# DCMotor1CTRL.net
KiCad netlist of a schematic drawn in Altium Designer
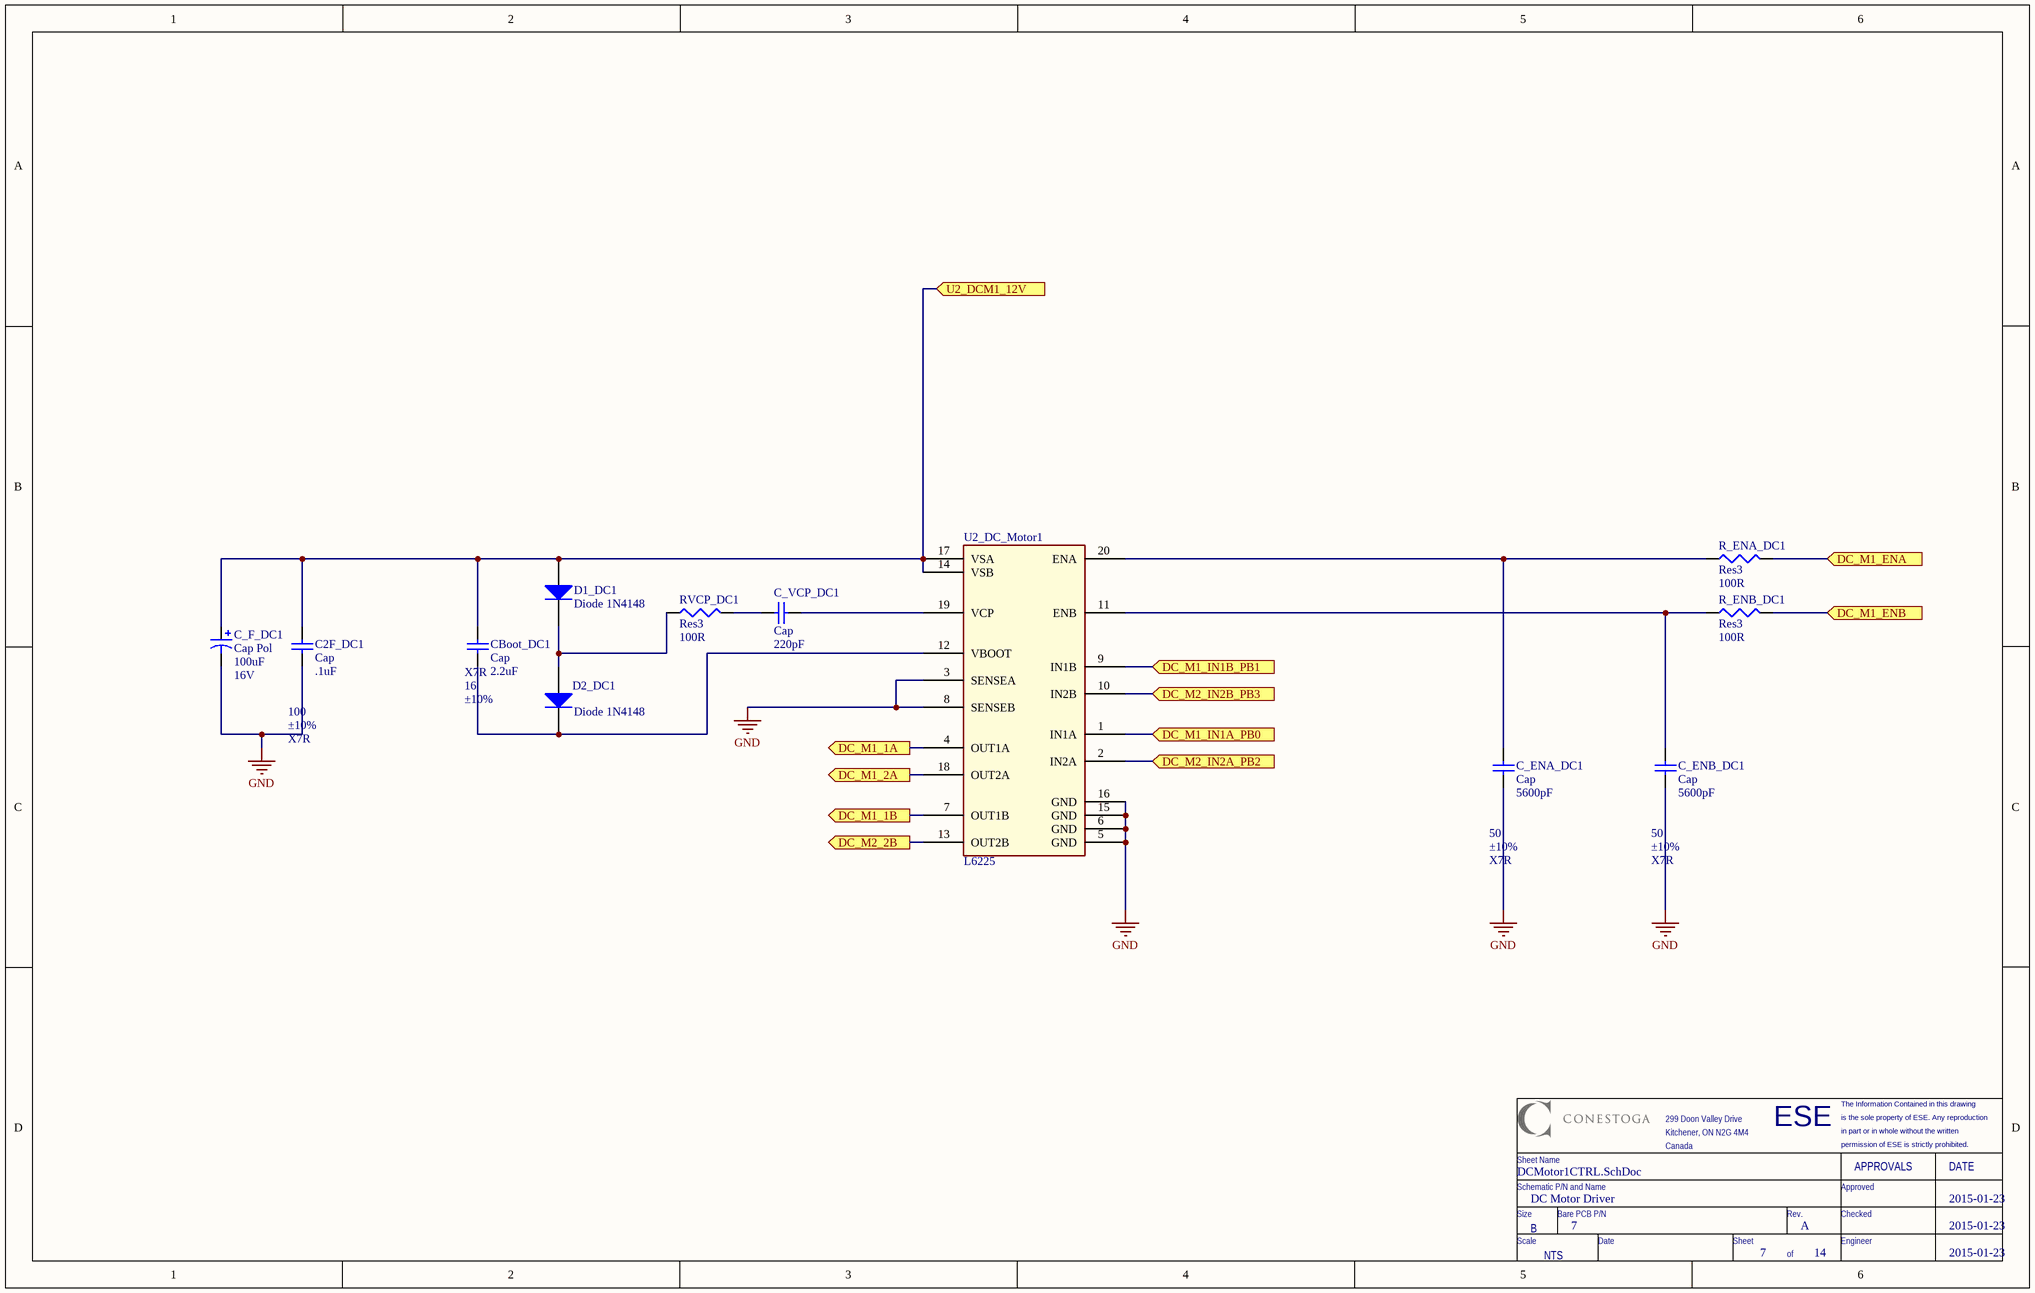
[diagram p0: DCMotor1CTRL.SchDoc]

(export (version "E")
  (design (tool "Eeschema 10.0.6"))
  (components
    (comp (ref "C2F_DC1")
      (value "Cap")
      (footprint "CAPC2012X09M")
      (description "CAP CER .1uF 100v X7R 0805")
      (fields
        (field (name "ALTIUM_VALUE") ".1uF")
        (field (name "MPN") "C0805C104K1RACTU")
        (field (name "WV") "100")
        (field (name "TOLERANCE") "±10%")
        (field (name "TYPE") "X7R")
      )
      (libsource (lib "esd_library") (part "CAP-X7R-.1uF-100V-±10%"))
    )
    (comp (ref "CBoot_DC1")
      (value "Cap")
      (footprint "CAPC2012X09M")
      (description "CAP CER 2.2uF 16v X7R 0805")
      (fields
        (field (name "ALTIUM_VALUE") "2.2uF")
        (field (name "MPN") "C0805C225K4RACTU")
        (field (name "WV") "16")
        (field (name "TOLERANCE") "±10%")
        (field (name "TYPE") "X7R")
      )
      (libsource (lib "esd_library") (part "CAP-X7R-2.2uF-16V-±10%"))
    )
    (comp (ref "C_ENA_DC1")
      (value "Cap")
      (footprint "CAPC2012X09M")
      (description "CAP CER 5600pF 50v X7R 0805")
      (fields
        (field (name "ALTIUM_VALUE") "5600pF")
        (field (name "MPN") "C0805C562K5RACTU")
        (field (name "WV") "50")
        (field (name "TOLERANCE") "±10%")
        (field (name "TYPE") "X7R")
      )
      (libsource (lib "esd_library") (part "CAP-X7R-5600pF-50V-±10%"))
    )
    (comp (ref "C_ENB_DC1")
      (value "Cap")
      (footprint "CAPC2012X09M")
      (description "CAP CER 5600pF 50v X7R 0805")
      (fields
        (field (name "ALTIUM_VALUE") "5600pF")
        (field (name "MPN") "C0805C562K5RACTU")
        (field (name "WV") "50")
        (field (name "TOLERANCE") "±10%")
        (field (name "TYPE") "X7R")
      )
      (libsource (lib "esd_library") (part "CAP-X7R-5600pF-50V-±10%"))
    )
    (comp (ref "C_F_DC1")
      (value "Cap Pol")
      (footprint "CAPACITOR_6.3MM")
      (description "CAP 85C 100uF ±20% 16V WX Series Aluminum Electrolytic")
      (fields
        (field (name "ALTIUM_VALUE") "100uF")
        (field (name "VOLTAGE") "16V")
        (field (name "MPN") "UWX1C101MCL1GB")
      )
      (libsource (lib "esd_library") (part "Cap Polar-100uF-16V"))
    )
    (comp (ref "C_VCP_DC1")
      (value "Cap")
      (footprint "CAPC2012X09M")
      (description "CAP CER 220pF 50v COG 0805")
      (fields (field (name "ALTIUM_VALUE") "220pF") (field (name "MPN") "C0805C221J5GACTU"))
      (libsource (lib "Caps$") (part "CAP-COG-220pF-50V-±5%"))
    )
    (comp (ref "D1_DC1")
      (value "Diode 1N4148")
      (footprint "zener_sod323")
      (description "High Conductance Fast Diode")
      (libsource (lib "esd_library") (part "Diode 1N4148"))
    )
    (comp (ref "D2_DC1")
      (value "Diode 1N4148")
      (footprint "zener_sod323")
      (description "High Conductance Fast Diode")
      (libsource (lib "esd_library") (part "Diode 1N4148"))
    )
    (comp (ref "RVCP_DC1")
      (value "Res3")
      (footprint "RESC2112X05M")
      (description "RES SMD 100R OHM 1% 1/8W 0805")
      (fields (field (name "ALTIUM_VALUE") "100R") (field (name "MPN") "CRCW0805100RFKEA"))
      (libsource (lib "esd_library") (part "Resistor_100R"))
    )
    (comp (ref "R_ENA_DC1")
      (value "Res3")
      (footprint "RESC2112X05M")
      (description "RES SMD 100R OHM 1% 1/8W 0805")
      (fields (field (name "ALTIUM_VALUE") "100R") (field (name "MPN") "CRCW0805100RFKEA"))
      (libsource (lib "esd_library") (part "Resistor_100R"))
    )
    (comp (ref "R_ENB_DC1")
      (value "Res3")
      (footprint "RESC2112X05M")
      (description "RES SMD 100R OHM 1% 1/8W 0805")
      (fields (field (name "ALTIUM_VALUE") "100R") (field (name "MPN") "CRCW0805100RFKEA"))
      (libsource (lib "esd_library") (part "Resistor_100R"))
    )
    (comp (ref "U2_DC_Motor1")
      (value "L6225")
      (footprint "POWERSOP20")
      (description "IC MOTOR DRIVER PAR 20POWERSO")
      (fields (field (name "MPN") "L6225PDTR"))
      (libsource (lib "esd_library") (part "L6225"))
    )
  )
  (nets
    (net (code "1") (name "/DC_M1_1A") (class "Default")
      (node (ref "U2_DC_Motor1") (pin "4") (pinfunction "OUT1A_4") (pintype "passive"))
    )
    (net (code "2") (name "/DC_M1_1B") (class "Default")
      (node (ref "U2_DC_Motor1") (pin "7") (pinfunction "OUT1B_7") (pintype "passive"))
    )
    (net (code "3") (name "/DC_M1_2A") (class "Default")
      (node (ref "U2_DC_Motor1") (pin "18") (pinfunction "OUT2A_18") (pintype "passive"))
    )
    (net (code "4") (name "/DC_M1_ENA") (class "Default")
      (node (ref "R_ENA_DC1") (pin "2") (pinfunction "2_2") (pintype "passive"))
    )
    (net (code "5") (name "/DC_M1_ENB") (class "Default")
      (node (ref "R_ENB_DC1") (pin "2") (pinfunction "2_2") (pintype "passive"))
    )
    (net (code "6") (name "/DC_M1_IN1A_PB0") (class "Default")
      (node (ref "U2_DC_Motor1") (pin "1") (pinfunction "IN1A_1") (pintype "passive"))
    )
    (net (code "7") (name "/DC_M1_IN1B_PB1") (class "Default")
      (node (ref "U2_DC_Motor1") (pin "9") (pinfunction "IN1B_9") (pintype "passive"))
    )
    (net (code "8") (name "/DC_M2_2B") (class "Default")
      (node (ref "U2_DC_Motor1") (pin "13") (pinfunction "OUT2B_13") (pintype "passive"))
    )
    (net (code "9") (name "/DC_M2_IN2A_PB2") (class "Default")
      (node (ref "U2_DC_Motor1") (pin "2") (pinfunction "IN2A_2") (pintype "passive"))
    )
    (net (code "10") (name "/DC_M2_IN2B_PB3") (class "Default")
      (node (ref "U2_DC_Motor1") (pin "10") (pinfunction "IN2B_10") (pintype "passive"))
    )
    (net (code "11") (name "/U2_DCM1_12V") (class "Default")
      (node (ref "C2F_DC1") (pin "2") (pinfunction "2_2") (pintype "passive"))
      (node (ref "CBoot_DC1") (pin "2") (pinfunction "2_2") (pintype "passive"))
      (node (ref "C_F_DC1") (pin "1") (pinfunction "1_1") (pintype "passive"))
      (node (ref "D1_DC1") (pin "A") (pinfunction "A_A") (pintype "passive"))
      (node (ref "U2_DC_Motor1") (pin "14") (pinfunction "VSB_14") (pintype "power_in"))
      (node (ref "U2_DC_Motor1") (pin "17") (pinfunction "VSA_17") (pintype "power_in"))
    )
    (net (code "12") (name "GND") (class "Default")
      (node (ref "C2F_DC1") (pin "1") (pinfunction "1_1") (pintype "passive"))
      (node (ref "C_ENA_DC1") (pin "1") (pinfunction "1_1") (pintype "passive"))
      (node (ref "C_ENB_DC1") (pin "1") (pinfunction "1_1") (pintype "passive"))
      (node (ref "C_F_DC1") (pin "2") (pinfunction "2_2") (pintype "passive"))
      (node (ref "U2_DC_Motor1") (pin "15") (pinfunction "GND_15") (pintype "power_in"))
      (node (ref "U2_DC_Motor1") (pin "16") (pinfunction "GND_16") (pintype "power_in"))
      (node (ref "U2_DC_Motor1") (pin "3") (pinfunction "SENSEA_3") (pintype "open_collector"))
      (node (ref "U2_DC_Motor1") (pin "5") (pinfunction "GND_5") (pintype "power_in"))
      (node (ref "U2_DC_Motor1") (pin "6") (pinfunction "GND_6") (pintype "power_in"))
      (node (ref "U2_DC_Motor1") (pin "8") (pinfunction "SENSEB_8") (pintype "power_in"))
    )
    (net (code "13") (name "Net-(C_VCP_DC1-Pad1)") (class "Default")
      (node (ref "C_VCP_DC1") (pin "1") (pinfunction "1_1") (pintype "passive"))
      (node (ref "RVCP_DC1") (pin "2") (pinfunction "2_2") (pintype "passive"))
    )
    (net (code "14") (name "Net-(D1_DC1-PadK)") (class "Default")
      (node (ref "D1_DC1") (pin "K") (pinfunction "K_K") (pintype "passive"))
      (node (ref "D2_DC1") (pin "A") (pinfunction "A_A") (pintype "passive"))
      (node (ref "RVCP_DC1") (pin "1") (pinfunction "1_1") (pintype "passive"))
    )
    (net (code "15") (name "Net-(U2_DC_Motor1-ENA)") (class "Default")
      (node (ref "C_ENA_DC1") (pin "2") (pinfunction "2_2") (pintype "passive"))
      (node (ref "R_ENA_DC1") (pin "1") (pinfunction "1_1") (pintype "passive"))
      (node (ref "U2_DC_Motor1") (pin "20") (pinfunction "ENA_20") (pintype "passive"))
    )
    (net (code "16") (name "Net-(U2_DC_Motor1-ENB)") (class "Default")
      (node (ref "C_ENB_DC1") (pin "2") (pinfunction "2_2") (pintype "passive"))
      (node (ref "R_ENB_DC1") (pin "1") (pinfunction "1_1") (pintype "passive"))
      (node (ref "U2_DC_Motor1") (pin "11") (pinfunction "ENB_11") (pintype "passive"))
    )
    (net (code "17") (name "Net-(U2_DC_Motor1-VBOOT)") (class "Default")
      (node (ref "CBoot_DC1") (pin "1") (pinfunction "1_1") (pintype "passive"))
      (node (ref "D2_DC1") (pin "K") (pinfunction "K_K") (pintype "passive"))
      (node (ref "U2_DC_Motor1") (pin "12") (pinfunction "VBOOT_12") (pintype "power_in"))
    )
    (net (code "18") (name "Net-(U2_DC_Motor1-VCP)") (class "Default")
      (node (ref "C_VCP_DC1") (pin "2") (pinfunction "2_2") (pintype "passive"))
      (node (ref "U2_DC_Motor1") (pin "19") (pinfunction "VCP_19") (pintype "power_in"))
    )
  )
)
